# SC10033E1.net
KiCad netlist of a schematic drawn in Altium Designer
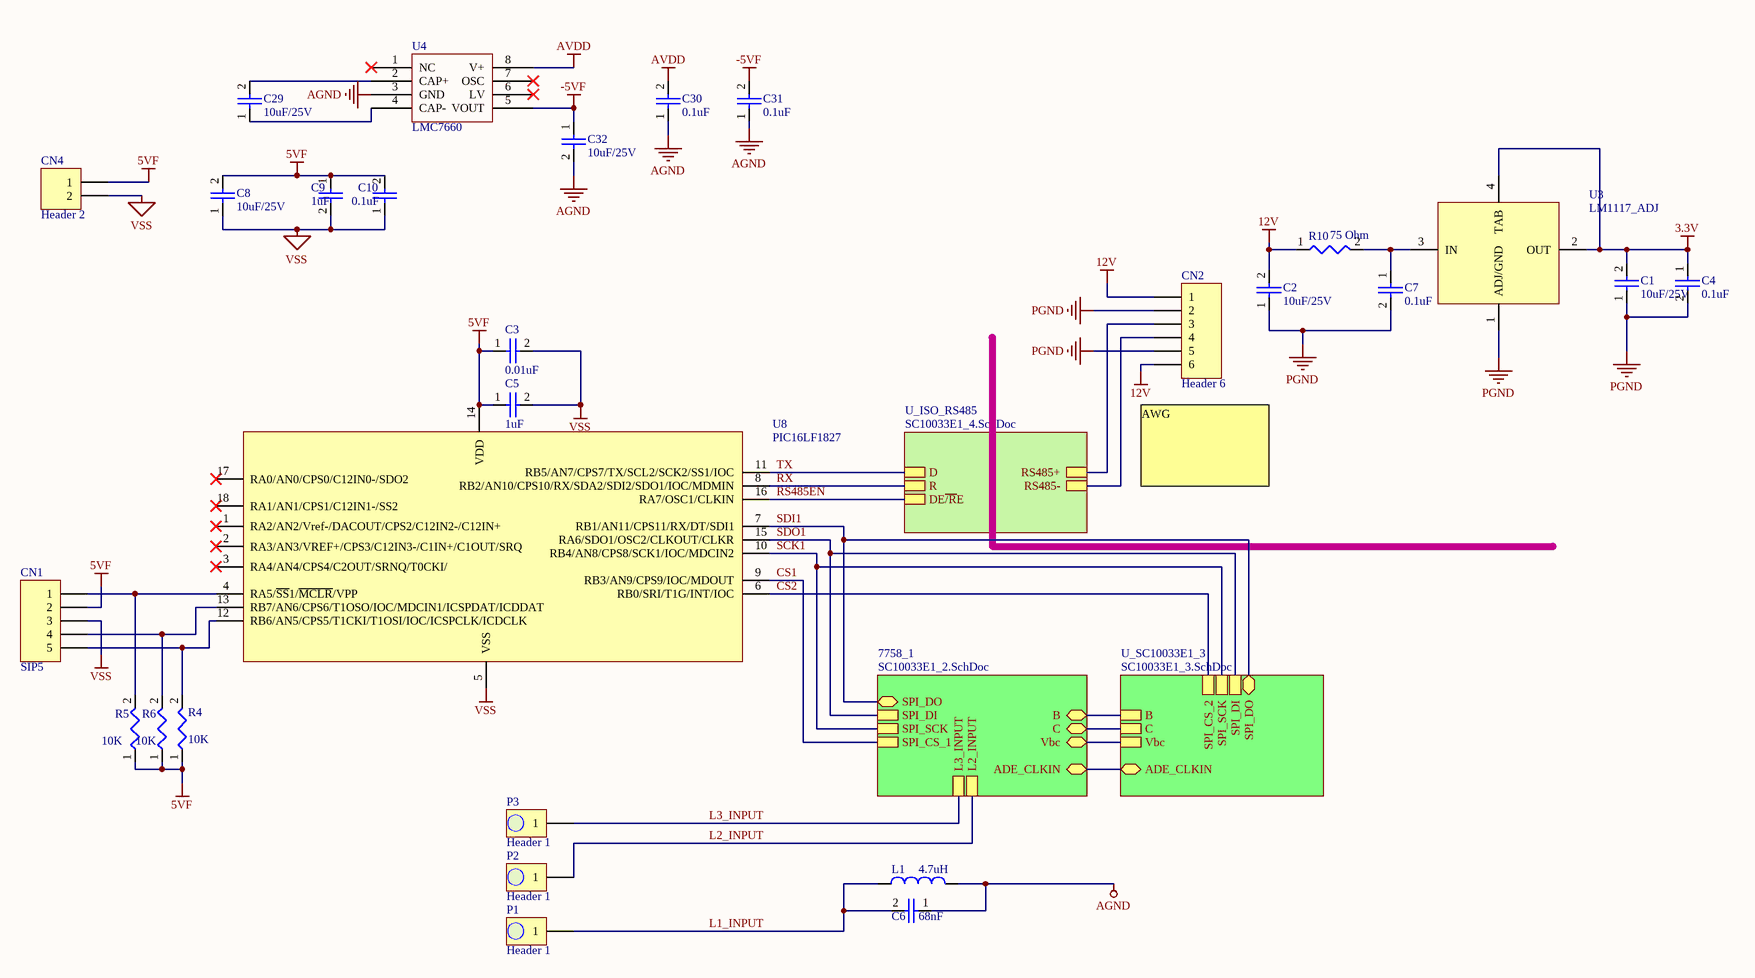
[diagram p0: SC10033E1.SchDoc]

(export (version "E")
  (design (tool "Eeschema 10.0.6"))
  (components
    (comp (ref "C1")
      (value "10uF/25V")
      (footprint "C1206")
      (description "CAP,CMCC,10uF,25V,10%,X7R,1206,SMD,ROHS")
      (fields (field (name "MANUFACTURER") "Murata") (field (name "Comment") "CAP"))
      (libsource (lib "enlogic") (part "CAP"))
    )
    (comp (ref "C2")
      (value "10uF/25V")
      (footprint "C1206")
      (description "CAP,CMCC,10uF,25V,10%,X7R,1206,SMD,ROHS")
      (fields (field (name "MANUFACTURER") "Murata") (field (name "Comment") "CAP"))
      (libsource (lib "enlogic") (part "CAP"))
    )
    (comp (ref "C3")
      (value "0.01uF")
      (footprint "C0805")
      (description "CAP SMD CR X7R 50V 10% 10nF 0805 ROHS")
      (fields (field (name "MANUFACTURER") "Murata") (field (name "Comment") "CAP"))
      (libsource (lib "enlogic") (part "CAP"))
    )
    (comp (ref "C4")
      (value "0.1uF")
      (footprint "C0805")
      (description "CAP SMD CR X7R 50V 10% 0.1uF 0805 ROHS")
      (fields (field (name "MANUFACTURER") "Murata") (field (name "Comment") "CAP"))
      (libsource (lib "enlogic") (part "CAP"))
    )
    (comp (ref "C5")
      (value "1uF")
      (footprint "C0805")
      (description "CAP SMD CR X7R 50V 10% 1uF 0805 ROHS")
      (fields (field (name "MANUFACTURER") "YAGEO") (field (name "Comment") "CAP"))
      (libsource (lib "enlogic") (part "CAP"))
    )
    (comp (ref "C6")
      (value "68nF")
      (footprint "C1206")
      (description "CAP SMD C0G 50V 5% 68nF 1206 ROHS")
      (fields (field (name "MANUFACTURER") "Murata") (field (name "Comment") "CAP"))
      (libsource (lib "enlogic") (part "CAP"))
    )
    (comp (ref "C7")
      (value "0.1uF")
      (footprint "C0805")
      (description "CAP SMD CR X7R 50V 10% 0.1uF 0805 ROHS")
      (fields (field (name "MANUFACTURER") "Murata") (field (name "Comment") "CAP"))
      (libsource (lib "enlogic") (part "CAP"))
    )
    (comp (ref "C8")
      (value "10uF/25V")
      (footprint "C1206")
      (description "CAP,CMCC,10uF,25V,10%,X7R,1206,SMD,ROHS")
      (fields (field (name "MANUFACTURER") "Murata") (field (name "Comment") "CAP"))
      (libsource (lib "enlogic") (part "CAP"))
    )
    (comp (ref "C9")
      (value "1uF")
      (footprint "C0805")
      (description "CAP SMD CR X7R 50V 10% 1uF 0805 ROHS")
      (fields (field (name "MANUFACTURER") "Murata") (field (name "Comment") "CAP"))
      (libsource (lib "enlogic") (part "CAP"))
    )
    (comp (ref "C10")
      (value "0.1uF")
      (footprint "C0805")
      (description "CAP SMD CR X7R 50V 10% 0.1uF 0805 ROHS")
      (fields (field (name "MANUFACTURER") "Murata") (field (name "Comment") "CAP"))
      (libsource (lib "enlogic") (part "CAP"))
    )
    (comp (ref "C29")
      (value "10uF/25V")
      (footprint "C1206")
      (description "CAP,CMCC,10uF,25V,10%,X7R,1206,SMD,ROHS")
      (fields (field (name "MANUFACTURER") "Murata") (field (name "Comment") "CAP"))
      (libsource (lib "enlogic") (part "CAP"))
    )
    (comp (ref "C30")
      (value "0.1uF")
      (footprint "C0805")
      (description "CAP SMD CR X7R 50V 10% 0.1uF 0805 ROHS")
      (fields (field (name "MANUFACTURER") "YAGEO") (field (name "Comment") "CAP"))
      (libsource (lib "enlogic") (part "CAP"))
    )
    (comp (ref "C31")
      (value "0.1uF")
      (footprint "C0805")
      (description "CAP SMD CR X7R 50V 10% 0.1uF 0805 ROHS")
      (fields (field (name "MANUFACTURER") "YAGEO") (field (name "Comment") "CAP"))
      (libsource (lib "enlogic") (part "CAP"))
    )
    (comp (ref "C32")
      (value "10uF/25V")
      (footprint "C1206")
      (description "CAP,CMCC,10uF,25V,10%,X7R,1206,SMD,ROHS")
      (fields (field (name "MANUFACTURER") "Murata") (field (name "Comment") "CAP"))
      (libsource (lib "enlogic") (part "CAP"))
    )
    (comp (ref "CN1")
      (value "SIP5")
      (footprint "SIP5")
      (description "CONNECTOR 5PIN,2.54PITCH,SIP-5")
      (fields (field (name "MANUFACTURER") "信荣"))
      (libsource (lib "enlogic") (part "Header 5"))
    )
    (comp (ref "CN2")
      (value "Header 6")
      (footprint "532590529-6P")
      (description "CONNECTOR 6PIN,3.5PITCH,PTH,ROHS")
      (fields (field (name "MANUFACTURER") "MOLEX"))
      (libsource (lib "enlogic") (part "Header 6"))
    )
    (comp (ref "CN4")
      (value "Header 2")
      (footprint "70551-2P")
      (description "CONNECTOR 2PIN,2.54PITCH,90 Degrees,PTH")
      (fields (field (name "MANUFACTURER") "MOLEX"))
      (libsource (lib "enlogic") (part "Header 2"))
    )
    (comp (ref "L1")
      (value "4.7uH")
      (footprint "L1008")
      (description "INDUCTOR 4.7uH 0.45A 5%,SRF = 50MHz,Q = 26, SMD 1008 ROHS")
      (fields (field (name "MANUFACTURER") "Wuerth Electronic") (field (name "Comment") "Inductor"))
      (libsource (lib "enlogic") (part "Inductor"))
    )
    (comp (ref "P1")
      (value "Header 1")
      (description "Header, 1-Pin")
      (libsource (lib "Enlogic_CN") (part "Header 1"))
    )
    (comp (ref "P2")
      (value "Header 1")
      (description "Header, 1-Pin")
      (libsource (lib "Enlogic_CN") (part "Header 1"))
    )
    (comp (ref "P3")
      (value "Header 1")
      (description "Header, 1-Pin")
      (libsource (lib "Enlogic_CN") (part "Header 1"))
    )
    (comp (ref "R4")
      (value "10K")
      (footprint "R0603")
      (description "RES THICK_FILM SMD 10K ohm 5% 1/10W ROHS 0603")
      (fields (field (name "MANUFACTURER") "YAGEO") (field (name "Comment") "RES"))
      (libsource (lib "enlogic") (part "RES"))
    )
    (comp (ref "R5")
      (value "10K")
      (footprint "R0603")
      (description "RES THICK_FILM SMD 10K ohm 5% 1/10W ROHS 0603")
      (fields (field (name "MANUFACTURER") "YAGEO") (field (name "Comment") "RES"))
      (libsource (lib "enlogic") (part "RES"))
    )
    (comp (ref "R6")
      (value "10K")
      (footprint "R0603")
      (description "RES THICK_FILM SMD 10K ohm 5% 1/10W ROHS 0603")
      (fields (field (name "MANUFACTURER") "YAGEO") (field (name "Comment") "RES"))
      (libsource (lib "enlogic") (part "RES"))
    )
    (comp (ref "R10")
      (value "75 Ohm")
      (footprint "R2512")
      (description "RES THICK_FILM SMD 75 ohm 5% 1W ROHS 2512")
      (fields (field (name "MANUFACTURER") "YAGEO") (field (name "Comment") "RES"))
      (libsource (lib "enlogic") (part "RES"))
    )
    (comp (ref "U3")
      (value "LM1117_ADJ")
      (footprint "DPAK-134")
      (description "IC REG VOLT +3.3V LDO 800MA DPAK ROHS")
      (fields (field (name "MANUFACTURER") "ST"))
      (libsource (lib "enlogic") (part "LM1117_ADJ"))
    )
    (comp (ref "U4")
      (value "LMC7660")
      (footprint "SOIC8")
      (description "IC CMOS Voltage Converters")
      (fields (field (name "MANUFACTURER") "National Semiconductor"))
      (libsource (lib "enlogic") (part "LMC7660"))
    )
    (comp (ref "U8")
      (value "PIC16LF1827")
      (footprint "SO18")
      (description "IC 8-bit UART SPI I2C,SOIC18-W,SMD,ROHS")
      (fields (field (name "MANUFACTURER") "Microchip"))
      (libsource (lib "enlogic") (part "PIC16LF1827"))
    )
  )
  (nets
    (net (code "1") (name "-5VF") (class "Default")
      (node (ref "C31") (pin "2") (pinfunction "2_2") (pintype "passive"))
      (node (ref "C32") (pin "1") (pinfunction "1_1") (pintype "passive"))
      (node (ref "U4") (pin "5") (pinfunction "VOUT_5") (pintype "passive"))
    )
    (net (code "5") (name "/CS1") (class "Default")
      (node (ref "U8") (pin "9") (pinfunction "RB3/AN9/CPS9/IOC/MDOUT_9") (pintype "passive"))
    )
    (net (code "6") (name "/CS2") (class "Default")
      (node (ref "U8") (pin "6") (pinfunction "RB0/SRI/T1G/INT/IOC_6") (pintype "passive"))
    )
    (net (code "7") (name "/L1_INPUT") (class "Default")
      (node (ref "C6") (pin "2") (pinfunction "2_2") (pintype "passive"))
      (node (ref "L1") (pin "1") (pinfunction "1_1") (pintype "passive"))
      (node (ref "P1") (pin "1") (pinfunction "1_1") (pintype "passive"))
    )
    (net (code "8") (name "/L2_INPUT") (class "Default")
      (node (ref "P2") (pin "1") (pinfunction "1_1") (pintype "passive"))
    )
    (net (code "9") (name "/L3_INPUT") (class "Default")
      (node (ref "P3") (pin "1") (pinfunction "1_1") (pintype "passive"))
    )
    (net (code "10") (name "/RS485+") (class "Default")
      (node (ref "CN2") (pin "3") (pinfunction "3_3") (pintype "passive"))
    )
    (net (code "11") (name "/RS485-") (class "Default")
      (node (ref "CN2") (pin "4") (pinfunction "4_4") (pintype "passive"))
    )
    (net (code "12") (name "/RS485EN") (class "Default")
      (node (ref "U8") (pin "16") (pinfunction "RA7/OSC1/CLKIN_16") (pintype "passive"))
    )
    (net (code "13") (name "/RX") (class "Default")
      (node (ref "U8") (pin "8") (pinfunction "RB2/AN10/CPS10/RX/SDA2/SDI2/SDO1/IOC/MDMIN_8") (pintype "passive"))
    )
    (net (code "14") (name "/SCK1") (class "Default")
      (node (ref "U8") (pin "10") (pinfunction "RB4/AN8/CPS8/SCK1/IOC/MDCIN2_10") (pintype "passive"))
    )
    (net (code "15") (name "/SDI1") (class "Default")
      (node (ref "U8") (pin "7") (pinfunction "RB1/AN11/CPS11/RX/DT/SDI1_7") (pintype "passive"))
    )
    (net (code "16") (name "/SDO1") (class "Default")
      (node (ref "U8") (pin "15") (pinfunction "RA6/SDO1/OSC2/CLKOUT/CLKR_15") (pintype "passive"))
    )
    (net (code "17") (name "/TX") (class "Default")
      (node (ref "U8") (pin "11") (pinfunction "RB5/AN7/CPS7/TX/SCL2/SCK2/SS1/IOC_11") (pintype "passive"))
    )
    (net (code "19") (name "3.3V") (class "Default")
      (node (ref "C1") (pin "2") (pinfunction "2_2") (pintype "passive"))
      (node (ref "C4") (pin "1") (pinfunction "1_1") (pintype "passive"))
      (node (ref "U3") (pin "2") (pinfunction "OUT_2") (pintype "passive"))
      (node (ref "U3") (pin "4") (pinfunction "TAB_4") (pintype "passive"))
    )
    (net (code "20") (name "5VF") (class "Default")
      (node (ref "C10") (pin "2") (pinfunction "2_2") (pintype "passive"))
      (node (ref "C3") (pin "1") (pinfunction "1_1") (pintype "passive"))
      (node (ref "C5") (pin "1") (pinfunction "1_1") (pintype "passive"))
      (node (ref "C8") (pin "2") (pinfunction "2_2") (pintype "passive"))
      (node (ref "C9") (pin "1") (pinfunction "1_1") (pintype "passive"))
      (node (ref "CN1") (pin "2") (pinfunction "2_2") (pintype "passive"))
      (node (ref "CN4") (pin "1") (pinfunction "1_1") (pintype "passive"))
      (node (ref "R4") (pin "1") (pinfunction "1_1") (pintype "passive"))
      (node (ref "R5") (pin "1") (pinfunction "1_1") (pintype "passive"))
      (node (ref "R6") (pin "1") (pinfunction "1_1") (pintype "passive"))
      (node (ref "U8") (pin "14") (pinfunction "VDD_14") (pintype "passive"))
    )
    (net (code "21") (name "12V") (class "Default")
      (node (ref "C2") (pin "2") (pinfunction "2_2") (pintype "passive"))
      (node (ref "CN2") (pin "1") (pinfunction "1_1") (pintype "passive"))
      (node (ref "CN2") (pin "6") (pinfunction "6_6") (pintype "passive"))
      (node (ref "R10") (pin "1") (pinfunction "1_1") (pintype "passive"))
    )
    (net (code "22") (name "AGND") (class "Default")
      (node (ref "C30") (pin "1") (pinfunction "1_1") (pintype "passive"))
      (node (ref "C31") (pin "1") (pinfunction "1_1") (pintype "passive"))
      (node (ref "C32") (pin "2") (pinfunction "2_2") (pintype "passive"))
      (node (ref "C6") (pin "1") (pinfunction "1_1") (pintype "passive"))
      (node (ref "L1") (pin "2") (pinfunction "2_2") (pintype "passive"))
      (node (ref "U4") (pin "3") (pinfunction "GND_3") (pintype "passive"))
    )
    (net (code "23") (name "AVDD") (class "Default")
      (node (ref "C30") (pin "2") (pinfunction "2_2") (pintype "passive"))
      (node (ref "U4") (pin "8") (pinfunction "V+_8") (pintype "passive"))
    )
    (net (code "24") (name "Net-(U3-IN)") (class "Default")
      (node (ref "C7") (pin "1") (pinfunction "1_1") (pintype "passive"))
      (node (ref "R10") (pin "2") (pinfunction "2_2") (pintype "passive"))
      (node (ref "U3") (pin "3") (pinfunction "IN_3") (pintype "passive"))
    )
    (net (code "25") (name "Net-(U4-CAP+)") (class "Default")
      (node (ref "C29") (pin "2") (pinfunction "2_2") (pintype "passive"))
      (node (ref "U4") (pin "2") (pinfunction "CAP+_2") (pintype "passive"))
    )
    (net (code "26") (name "Net-(U4-CAP-)") (class "Default")
      (node (ref "C29") (pin "1") (pinfunction "1_1") (pintype "passive"))
      (node (ref "U4") (pin "4") (pinfunction "CAP-_4") (pintype "passive"))
    )
    (net (code "27") (name "Net-(U8-RA5{slash}~{SS}1{slash}~{MCLR}{slash}VPP)") (class "Default")
      (node (ref "CN1") (pin "1") (pinfunction "1_1") (pintype "passive"))
      (node (ref "R5") (pin "2") (pinfunction "2_2") (pintype "passive"))
      (node (ref "U8") (pin "4") (pinfunction "RA5/~{SS}1/~{MCLR}/VPP_4") (pintype "passive"))
    )
    (net (code "28") (name "Net-(U8-RB6{slash}AN5{slash}CPS5{slash}T1CKI{slash}T1OSI{slash}IOC{slash}ICSPCLK{slash}ICDCLK)") (class "Default")
      (node (ref "CN1") (pin "5") (pinfunction "5_5") (pintype "passive"))
      (node (ref "R4") (pin "2") (pinfunction "2_2") (pintype "passive"))
      (node (ref "U8") (pin "12") (pinfunction "RB6/AN5/CPS5/T1CKI/T1OSI/IOC/ICSPCLK/ICDCLK_12") (pintype "passive"))
    )
    (net (code "29") (name "Net-(U8-RB7{slash}AN6{slash}CPS6{slash}T1OSO{slash}IOC{slash}MDCIN1{slash}ICSPDAT{slash}ICDDAT)") (class "Default")
      (node (ref "CN1") (pin "4") (pinfunction "4_4") (pintype "passive"))
      (node (ref "R6") (pin "2") (pinfunction "2_2") (pintype "passive"))
      (node (ref "U8") (pin "13") (pinfunction "RB7/AN6/CPS6/T1OSO/IOC/MDCIN1/ICSPDAT/ICDDAT_13") (pintype "passive"))
    )
    (net (code "30") (name "PGND") (class "Default")
      (node (ref "C1") (pin "1") (pinfunction "1_1") (pintype "passive"))
      (node (ref "C2") (pin "1") (pinfunction "1_1") (pintype "passive"))
      (node (ref "C4") (pin "2") (pinfunction "2_2") (pintype "passive"))
      (node (ref "C7") (pin "2") (pinfunction "2_2") (pintype "passive"))
      (node (ref "CN2") (pin "2") (pinfunction "2_2") (pintype "passive"))
      (node (ref "CN2") (pin "5") (pinfunction "5_5") (pintype "passive"))
      (node (ref "U3") (pin "1") (pinfunction "ADJ/GND_1") (pintype "passive"))
    )
    (net (code "31") (name "VSS") (class "Default")
      (node (ref "C10") (pin "1") (pinfunction "1_1") (pintype "passive"))
      (node (ref "C3") (pin "2") (pinfunction "2_2") (pintype "passive"))
      (node (ref "C5") (pin "2") (pinfunction "2_2") (pintype "passive"))
      (node (ref "C8") (pin "1") (pinfunction "1_1") (pintype "passive"))
      (node (ref "C9") (pin "2") (pinfunction "2_2") (pintype "passive"))
      (node (ref "CN1") (pin "3") (pinfunction "3_3") (pintype "passive"))
      (node (ref "CN4") (pin "2") (pinfunction "2_2") (pintype "passive"))
      (node (ref "U8") (pin "5") (pinfunction "VSS_5") (pintype "passive"))
    )
    (net (code "32") (name "unconnected-(U4-LV-Pad6)") (class "Default")
      (node (ref "U4") (pin "6") (pinfunction "LV_6") (pintype "passive+no_connect"))
    )
    (net (code "33") (name "unconnected-(U4-NC-Pad1)") (class "Default")
      (node (ref "U4") (pin "1") (pinfunction "NC_1") (pintype "passive+no_connect"))
    )
    (net (code "34") (name "unconnected-(U4-OSC-Pad7)") (class "Default")
      (node (ref "U4") (pin "7") (pinfunction "OSC_7") (pintype "passive+no_connect"))
    )
    (net (code "35") (name "unconnected-(U8-RA0{slash}AN0{slash}CPS0{slash}C12IN0-{slash}SDO2-Pad17)") (class "Default")
      (node (ref "U8") (pin "17") (pinfunction "RA0/AN0/CPS0/C12IN0-/SDO2_17") (pintype "passive+no_connect"))
    )
    (net (code "36") (name "unconnected-(U8-RA1{slash}AN1{slash}CPS1{slash}C12IN1-{slash}SS2-Pad18)") (class "Default")
      (node (ref "U8") (pin "18") (pinfunction "RA1/AN1/CPS1/C12IN1-/SS2_18") (pintype "passive+no_connect"))
    )
    (net (code "37") (name "unconnected-(U8-RA2{slash}AN2{slash}Vref-{slash}DACOUT{slash}CPS2{slash}C12IN2-{slash}C12IN+-Pad1)") (class "Default")
      (node (ref "U8") (pin "1") (pinfunction "RA2/AN2/Vref-/DACOUT/CPS2/C12IN2-/C12IN+_1") (pintype "passive+no_connect"))
    )
    (net (code "38") (name "unconnected-(U8-RA3{slash}AN3{slash}VREF+{slash}CPS3{slash}C12IN3-{slash}C1IN+{slash}C1OUT{slash}SRQ-Pad2)") (class "Default")
      (node (ref "U8") (pin "2") (pinfunction "RA3/AN3/VREF+/CPS3/C12IN3-/C1IN+/C1OUT/SRQ_2") (pintype "passive+no_connect"))
    )
    (net (code "39") (name "unconnected-(U8-RA4{slash}AN4{slash}CPS4{slash}C2OUT{slash}SRNQ{slash}T0CKI{slash}-Pad3)") (class "Default")
      (node (ref "U8") (pin "3") (pinfunction "RA4/AN4/CPS4/C2OUT/SRNQ/T0CKI/_3") (pintype "passive+no_connect"))
    )
  )
)
